# Ham-Dip-V2-005.net
KiCad netlist of a schematic drawn in EAGLE
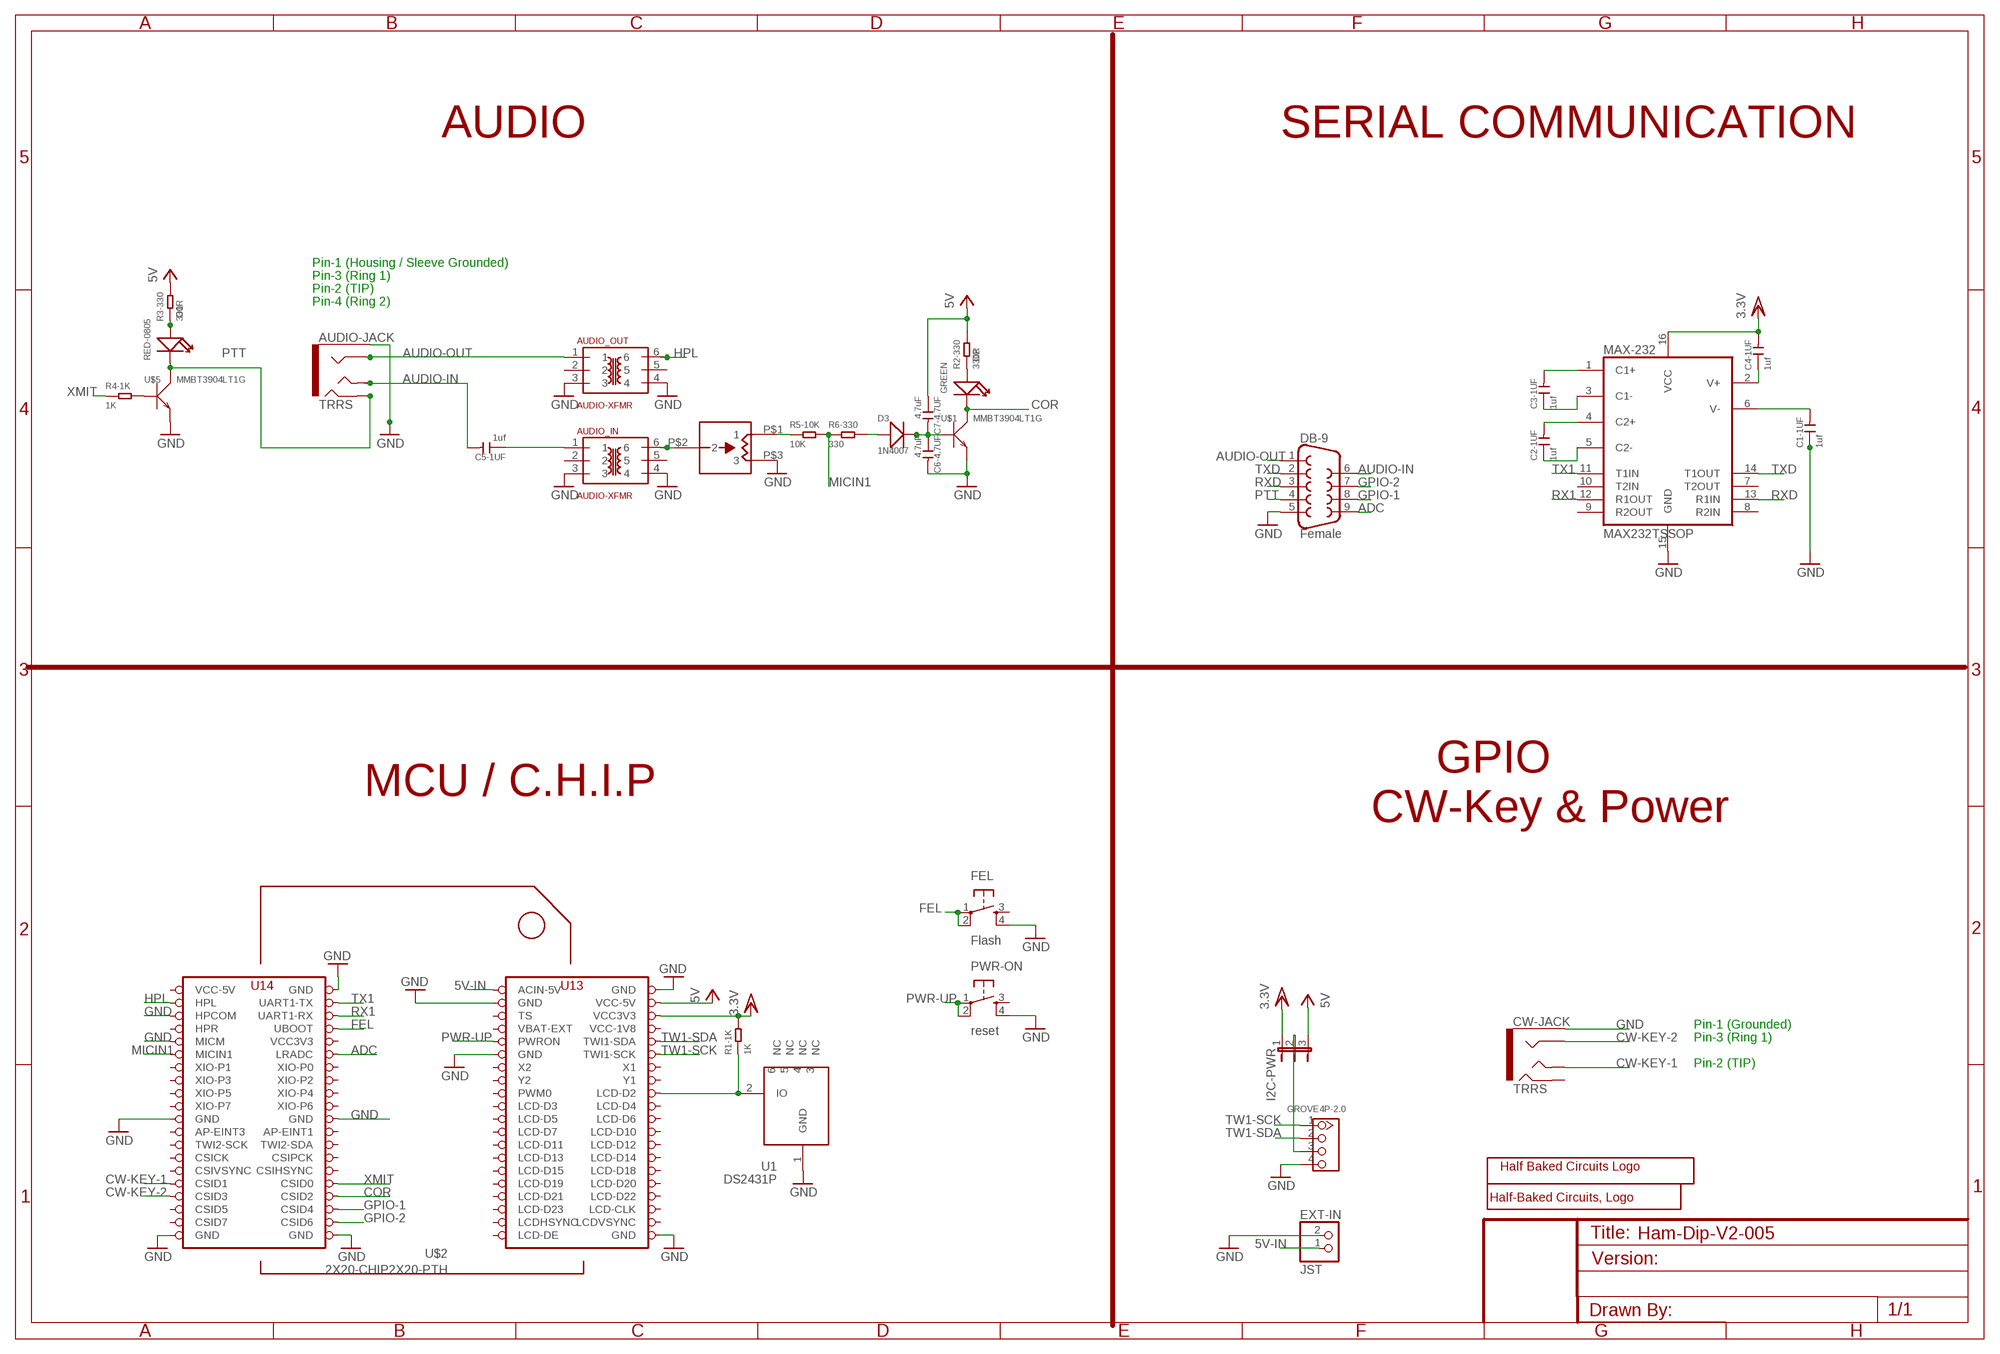
[diagram p0: schematic, sheet 1]

(export (version "E")
  (design (tool "Eeschema 10.0.6"))
  (components
    (comp (ref "AUDIO-JACK")
      (value "TRRS")
      (footprint "eagle-import:AUDIO-JACK-TRRS-SMD")
      (libsource (lib "eagle-import") (part "AUDIO-JACK3"))
    )
    (comp (ref "AUDIO_IN")
      (value "AUDIO-XFMR")
      (footprint "eagle-import:SM-LP-5001")
      (libsource (lib "eagle-import") (part "SM-LP-5001"))
    )
    (comp (ref "AUDIO_OUT")
      (value "AUDIO-XFMR")
      (footprint "eagle-import:SM-LP-5001")
      (libsource (lib "eagle-import") (part "SM-LP-5001"))
    )
    (comp (ref "C1-1UF")
      (value "1uf")
      (footprint "eagle-import:C0805")
      (fields (field (name "MPN") "CC0805KKX7R8BB105"))
      (libsource (lib "eagle-import") (part "CERAMIC-1UF-25V-10%-X7R(0805)"))
    )
    (comp (ref "C2-1UF")
      (value "1uf")
      (footprint "eagle-import:C0805")
      (fields (field (name "MPN") "CC0805KKX7R8BB105"))
      (libsource (lib "eagle-import") (part "CERAMIC-1UF-25V-10%-X7R(0805)"))
    )
    (comp (ref "C3-1UF")
      (value "1uf")
      (footprint "eagle-import:C0805")
      (fields (field (name "MPN") "CC0805KKX7R8BB105"))
      (libsource (lib "eagle-import") (part "CERAMIC-1UF-25V-10%-X7R(0805)"))
    )
    (comp (ref "C4-1UF")
      (value "1uf")
      (footprint "eagle-import:C0805")
      (fields (field (name "MPN") "CC0805KKX7R8BB105"))
      (libsource (lib "eagle-import") (part "CERAMIC-1UF-25V-10%-X7R(0805)"))
    )
    (comp (ref "C5-1UF")
      (value "1uf")
      (footprint "eagle-import:C0805")
      (fields (field (name "MPN") "CC0805KKX7R8BB105"))
      (libsource (lib "eagle-import") (part "CERAMIC-1UF-25V-10%-X7R(0805)"))
    )
    (comp (ref "C6-4.7UF")
      (value "4.7uF")
      (footprint "eagle-import:C0805")
      (fields (field (name "MPN") "CC0805KKX7R8BB105"))
      (libsource (lib "eagle-import") (part "CERAMIC-1UF-25V-10%-X7R(0805)"))
    )
    (comp (ref "C7-4.7UF")
      (value "4.7uF")
      (footprint "eagle-import:C0805")
      (fields (field (name "MPN") "CC0805KKX7R8BB105"))
      (libsource (lib "eagle-import") (part "CERAMIC-1UF-25V-10%-X7R(0805)"))
    )
    (comp (ref "CW-JACK")
      (value "TRRS")
      (footprint "eagle-import:AUDIO-JACK-TRRS-SMD")
      (libsource (lib "eagle-import") (part "AUDIO-JACK3"))
    )
    (comp (ref "D1")
      (value "RED-0805")
      (footprint "eagle-import:LED-0805")
      (fields (field (name "MPN") "17-215SURC/S530-A2/TR8"))
      (libsource (lib "eagle-import") (part "SMD-LED-CLEAR-RED(0805)"))
    )
    (comp (ref "D2")
      (value "GREEN")
      (footprint "eagle-import:LED-0805")
      (fields (field (name "MPN") "17-215SURC/S530-A2/TR8"))
      (libsource (lib "eagle-import") (part "SMD-LED-CLEAR-RED(0805)"))
    )
    (comp (ref "D3")
      (value "1N4007")
      (footprint "eagle-import:DO-214AC")
      (libsource (lib "eagle-import") (part "DIODE-GEN-PURPOSE-1KV-1A(DO-214AC)"))
    )
    (comp (ref "DB-9")
      (value "Female")
      (footprint "eagle-import:DB9")
      (libsource (lib "eagle-import") (part "DB9FEMALE"))
    )
    (comp (ref "EXT-IN")
      (value "JST")
      (footprint "eagle-import:JST-PH-2-THM")
      (libsource (lib "eagle-import") (part "JST_2PIN-THM"))
    )
    (comp (ref "FEL")
      (value "Flash")
      (footprint "eagle-import:TACTILE_SWITCH_SMD")
      (libsource (lib "eagle-import") (part "TAC_SWITCHSMD"))
    )
    (comp (ref "GROVE")
      (value "4P-2.0")
      (footprint "eagle-import:HW4-2.0")
      (libsource (lib "eagle-import") (part "GROVE-CONNECTOR-DIP(4P-2.0)"))
    )
    (comp (ref "I2C-PWR")
      (value "JP2E")
      (footprint "eagle-import:JP2")
      (libsource (lib "eagle-import") (part "JP2E"))
    )
    (comp (ref "MAX-232")
      (value "MAX232TSSOP")
      (footprint "eagle-import:TSSOP16")
      (libsource (lib "eagle-import") (part "MAX232TSSOP"))
    )
    (comp (ref "MIC-LVL")
      (value "1K")
      (footprint "eagle-import:TC33X")
      (libsource (lib "eagle-import") (part "TC33X"))
    )
    (comp (ref "PWR-ON")
      (value "reset")
      (footprint "eagle-import:TACTILE_SWITCH_SMD")
      (libsource (lib "eagle-import") (part "TAC_SWITCHSMD"))
    )
    (comp (ref "R1-1K")
      (value "1K")
      (footprint "eagle-import:R0805")
      (fields (field (name "MPN") "RC0805JR-07220RL"))
      (libsource (lib "eagle-import") (part "SMD-RES-220R-5%-1/8W(0805)"))
    )
    (comp (ref "R2-330")
      (value "330R")
      (footprint "eagle-import:R0805")
      (fields (field (name "MPN") "RC0805JR-07220RL"))
      (libsource (lib "eagle-import") (part "SMD-RES-220R-5%-1/8W(0805)"))
    )
    (comp (ref "R3-330")
      (value "330R")
      (footprint "eagle-import:R0805")
      (fields (field (name "MPN") "RC0805JR-07220RL"))
      (libsource (lib "eagle-import") (part "SMD-RES-220R-5%-1/8W(0805)"))
    )
    (comp (ref "R4-1K")
      (value "1K")
      (footprint "eagle-import:R0805")
      (fields (field (name "MPN") "RC0805JR-07220RL"))
      (libsource (lib "eagle-import") (part "SMD-RES-220R-5%-1/8W(0805)"))
    )
    (comp (ref "R5-10K")
      (value "10K")
      (footprint "eagle-import:R0805")
      (fields (field (name "MPN") "RC0805FR-0710KL"))
      (libsource (lib "eagle-import") (part "SMD-RES-10K-1%-1/8W(0805)"))
    )
    (comp (ref "R6-330")
      (value "330")
      (footprint "eagle-import:R0805")
      (fields (field (name "MPN") "RC0805JR-07220RL"))
      (libsource (lib "eagle-import") (part "SMD-RES-220R-5%-1/8W(0805)"))
    )
    (comp (ref "U$1")
      (value "MMBT3904LT1G")
      (footprint "eagle-import:SOT-23")
      (libsource (lib "eagle-import") (part "SMD-TRANSISTORS-NPN-40V-200MA-MMBT3904LT1G(SOT-23)"))
    )
    (comp (ref "U$2")
      (value "2X20-CHIP2X20-PTH")
      (footprint "eagle-import:2X20CHIP-TH")
      (fields (field (name "VENDOR_PART_NUMBER") "AWHW40-G-SMD-R (single)"))
      (libsource (lib "eagle-import") (part "2X20-CHIP2X20-PTH-CHIP_A"))
    )
    (comp (ref "U$3")
      (value "HBC-LOGO")
      (footprint "eagle-import:HBC-LOGO")
      (libsource (lib "eagle-import") (part "HBC-LOGO"))
    )
    (comp (ref "U$4")
      (value "HAM-DIP")
      (footprint "eagle-import:HAM-DIP")
      (libsource (lib "eagle-import") (part "HAM-DIP"))
    )
    (comp (ref "U$5")
      (value "MMBT3904LT1G")
      (footprint "eagle-import:SOT-23")
      (libsource (lib "eagle-import") (part "SMD-TRANSISTORS-NPN-40V-200MA-MMBT3904LT1G(SOT-23)"))
    )
    (comp (ref "U1")
      (value "DS2431P")
      (footprint "eagle-import:TSOC6")
      (fields (field (name "MFG") "DIGIKEY") (field (name "VENDOR_PART_NUMBER") "DS2431P+T&R"))
      (libsource (lib "eagle-import") (part "DS2431P"))
    )
  )
  (nets
    (net (code "1") (name "/5V-IN") (class "Default")
      (node (ref "EXT-IN") (pin "1") (pinfunction "2_1") (pintype "passive"))
      (node (ref "U$2") (pin "CHG-IN") (pinfunction "ACIN-5V_CHG-IN") (pintype "passive"))
    )
    (net (code "2") (name "/ADC") (class "Default")
      (node (ref "DB-9") (pin "9") (pinfunction "9_9") (pintype "passive"))
      (node (ref "U$2") (pin "LRADC") (pinfunction "LRADC_LRADC") (pintype "passive"))
    )
    (net (code "3") (name "/AUDIO-IN") (class "Default")
      (node (ref "AUDIO-JACK") (pin "TIP") (pinfunction "TIP_TIP") (pintype "bidirectional"))
      (node (ref "C5-1UF") (pin "2") (pinfunction "2_2") (pintype "passive"))
      (node (ref "DB-9") (pin "6") (pinfunction "6_6") (pintype "passive"))
    )
    (net (code "4") (name "/AUDIO-OUT") (class "Default")
      (node (ref "AUDIO-JACK") (pin "RING1") (pinfunction "RING1_RING1") (pintype "bidirectional"))
      (node (ref "AUDIO_OUT") (pin "1") (pinfunction "1_1") (pintype "bidirectional"))
      (node (ref "DB-9") (pin "1") (pinfunction "1_1") (pintype "passive"))
    )
    (net (code "5") (name "/COR") (class "Default")
      (node (ref "D2") (pin "-") (pinfunction "-_-") (pintype "passive"))
      (node (ref "U$1") (pin "3") (pinfunction "C_3") (pintype "passive"))
      (node (ref "U$2") (pin "CSID2") (pinfunction "CSID2_CSID2") (pintype "passive"))
    )
    (net (code "6") (name "/CW-KEY-1") (class "Default")
      (node (ref "CW-JACK") (pin "TIP") (pinfunction "TIP_TIP") (pintype "bidirectional"))
      (node (ref "U$2") (pin "CSID1") (pinfunction "CSID1_CSID1") (pintype "passive"))
    )
    (net (code "7") (name "/CW-KEY-2") (class "Default")
      (node (ref "CW-JACK") (pin "RING1") (pinfunction "RING1_RING1") (pintype "bidirectional"))
      (node (ref "U$2") (pin "CSID3") (pinfunction "CSID3_CSID3") (pintype "passive"))
    )
    (net (code "8") (name "/FEL") (class "Default")
      (node (ref "FEL") (pin "1") (pinfunction "1_1") (pintype "passive"))
      (node (ref "FEL") (pin "2") (pinfunction "2_2") (pintype "passive"))
      (node (ref "U$2") (pin "FEL") (pinfunction "UBOOT_FEL") (pintype "passive"))
    )
    (net (code "9") (name "/GPIO-1") (class "Default")
      (node (ref "DB-9") (pin "8") (pinfunction "8_8") (pintype "passive"))
      (node (ref "U$2") (pin "CSID4") (pinfunction "CSID4_CSID4") (pintype "passive"))
    )
    (net (code "10") (name "/GPIO-2") (class "Default")
      (node (ref "DB-9") (pin "7") (pinfunction "7_7") (pintype "passive"))
      (node (ref "U$2") (pin "CSID6") (pinfunction "CSID6_CSID6") (pintype "passive"))
    )
    (net (code "11") (name "/HPL") (class "Default")
      (node (ref "AUDIO_OUT") (pin "6") (pinfunction "6_6") (pintype "bidirectional"))
      (node (ref "U$2") (pin "HPL") (pinfunction "HPL_HPL") (pintype "passive"))
    )
    (net (code "12") (name "/MICIN1") (class "Default")
      (node (ref "R5-10K") (pin "2") (pinfunction "2_2") (pintype "passive"))
      (node (ref "R6-330") (pin "1") (pinfunction "1_1") (pintype "passive"))
      (node (ref "U$2") (pin "MICIN1") (pinfunction "MICIN1_MICIN1") (pintype "passive"))
    )
    (net (code "13") (name "/PTT") (class "Default")
      (node (ref "AUDIO-JACK") (pin "RING2") (pinfunction "RING2_RING2") (pintype "bidirectional"))
      (node (ref "D1") (pin "-") (pinfunction "-_-") (pintype "passive"))
      (node (ref "DB-9") (pin "4") (pinfunction "4_4") (pintype "passive"))
      (node (ref "U$5") (pin "3") (pinfunction "C_3") (pintype "passive"))
    )
    (net (code "14") (name "/PWR-UP") (class "Default")
      (node (ref "PWR-ON") (pin "1") (pinfunction "1_1") (pintype "passive"))
      (node (ref "PWR-ON") (pin "2") (pinfunction "2_2") (pintype "passive"))
      (node (ref "U$2") (pin "PWRON") (pinfunction "PWRON_PWRON") (pintype "passive"))
    )
    (net (code "15") (name "/RX1") (class "Default")
      (node (ref "MAX-232") (pin "12") (pinfunction "R1OUT_12") (pintype "output"))
      (node (ref "U$2") (pin "UART1-RX") (pinfunction "UART1-RX_UART1-RX") (pintype "passive"))
    )
    (net (code "16") (name "/RXD") (class "Default")
      (node (ref "DB-9") (pin "3") (pinfunction "3_3") (pintype "passive"))
      (node (ref "MAX-232") (pin "13") (pinfunction "R1IN_13") (pintype "input"))
    )
    (net (code "17") (name "/TW1-SCK") (class "Default")
      (node (ref "GROVE") (pin "1") (pinfunction "1_1") (pintype "bidirectional"))
      (node (ref "U$2") (pin "TWI1-SCK") (pinfunction "TWI1-SCK_TWI1-SCK") (pintype "passive"))
    )
    (net (code "18") (name "/TW1-SDA") (class "Default")
      (node (ref "GROVE") (pin "2") (pinfunction "2_2") (pintype "bidirectional"))
      (node (ref "U$2") (pin "TWI1-SDA") (pinfunction "TWI1-SDA_TWI1-SDA") (pintype "passive"))
    )
    (net (code "19") (name "/TX1") (class "Default")
      (node (ref "MAX-232") (pin "11") (pinfunction "T1IN_11") (pintype "input"))
      (node (ref "U$2") (pin "UART1-TX") (pinfunction "UART1-TX_UART1-TX") (pintype "passive"))
    )
    (net (code "20") (name "/TXD") (class "Default")
      (node (ref "DB-9") (pin "2") (pinfunction "2_2") (pintype "passive"))
      (node (ref "MAX-232") (pin "14") (pinfunction "T1OUT_14") (pintype "output"))
    )
    (net (code "21") (name "/VCC-1V8") (class "Default")
      (node (ref "U$2") (pin "VCC1V8") (pinfunction "VCC-1V8_VCC1V8") (pintype "power_in"))
    )
    (net (code "22") (name "/VCC-5V") (class "Default")
      (node (ref "U$2") (pin "VCC5V@1") (pinfunction "VCC-5V_VCC5V@1") (pintype "power_in"))
    )
    (net (code "23") (name "/VCC3V3") (class "Default")
      (node (ref "U$2") (pin "VCC3V3@1") (pinfunction "VCC3V3_VCC3V3@1") (pintype "power_in"))
    )
    (net (code "24") (name "/XMIT") (class "Default")
      (node (ref "R4-1K") (pin "1") (pinfunction "1_1") (pintype "passive"))
      (node (ref "U$2") (pin "CSID0") (pinfunction "CSID0_CSID0") (pintype "passive"))
    )
    (net (code "25") (name "3.3V") (class "Default")
      (node (ref "C4-1UF") (pin "2") (pinfunction "2_2") (pintype "passive"))
      (node (ref "I2C-PWR") (pin "1") (pinfunction "1_1") (pintype "passive"))
      (node (ref "MAX-232") (pin "16") (pinfunction "VCC_16") (pintype "bidirectional"))
      (node (ref "R1-1K") (pin "2") (pinfunction "2_2") (pintype "passive"))
      (node (ref "U$2") (pin "VCC3V3") (pinfunction "VCC3V3_VCC3V3") (pintype "power_in"))
    )
    (net (code "26") (name "5V") (class "Default")
      (node (ref "C7-4.7UF") (pin "1") (pinfunction "1_1") (pintype "passive"))
      (node (ref "I2C-PWR") (pin "3") (pinfunction "3_3") (pintype "passive"))
      (node (ref "R2-330") (pin "2") (pinfunction "2_2") (pintype "passive"))
      (node (ref "R3-330") (pin "2") (pinfunction "2_2") (pintype "passive"))
      (node (ref "U$2") (pin "VCC5V@0") (pinfunction "VCC-5V_VCC5V@0") (pintype "power_in"))
    )
    (net (code "27") (name "GND") (class "Default")
      (node (ref "AUDIO-JACK") (pin "EARTH") (pinfunction "EARTH_EARTH") (pintype "bidirectional"))
      (node (ref "AUDIO_IN") (pin "3") (pinfunction "3_3") (pintype "bidirectional"))
      (node (ref "AUDIO_IN") (pin "4") (pinfunction "4_4") (pintype "bidirectional"))
      (node (ref "AUDIO_OUT") (pin "3") (pinfunction "3_3") (pintype "bidirectional"))
      (node (ref "AUDIO_OUT") (pin "4") (pinfunction "4_4") (pintype "bidirectional"))
      (node (ref "C1-1UF") (pin "1") (pinfunction "1_1") (pintype "passive"))
      (node (ref "C6-4.7UF") (pin "2") (pinfunction "2_2") (pintype "passive"))
      (node (ref "CW-JACK") (pin "EARTH") (pinfunction "EARTH_EARTH") (pintype "bidirectional"))
      (node (ref "DB-9") (pin "5") (pinfunction "5_5") (pintype "passive"))
      (node (ref "EXT-IN") (pin "2") (pinfunction "1_2") (pintype "passive"))
      (node (ref "FEL") (pin "4") (pinfunction "4_4") (pintype "passive"))
      (node (ref "GROVE") (pin "4") (pinfunction "4_4") (pintype "bidirectional"))
      (node (ref "MAX-232") (pin "15") (pinfunction "GND_15") (pintype "bidirectional"))
      (node (ref "MIC-LVL") (pin "P$3") (pinfunction "3_P$3") (pintype "bidirectional"))
      (node (ref "PWR-ON") (pin "4") (pinfunction "4_4") (pintype "passive"))
      (node (ref "U$1") (pin "2") (pinfunction "E_2") (pintype "passive"))
      (node (ref "U$2") (pin "GND@1") (pinfunction "GND_GND@1") (pintype "power_in"))
      (node (ref "U$2") (pin "GND@10") (pinfunction "GND_GND@10") (pintype "power_in"))
      (node (ref "U$2") (pin "GND@2") (pinfunction "GND_GND@2") (pintype "power_in"))
      (node (ref "U$2") (pin "GND@3") (pinfunction "GND_GND@3") (pintype "power_in"))
      (node (ref "U$2") (pin "GND@4") (pinfunction "GND_GND@4") (pintype "power_in"))
      (node (ref "U$2") (pin "GND@5") (pinfunction "GND_GND@5") (pintype "power_in"))
      (node (ref "U$2") (pin "GND@6") (pinfunction "GND_GND@6") (pintype "power_in"))
      (node (ref "U$2") (pin "GND@7") (pinfunction "GND_GND@7") (pintype "power_in"))
      (node (ref "U$2") (pin "GND@8") (pinfunction "GND_GND@8") (pintype "power_in"))
      (node (ref "U$2") (pin "HPCOM") (pinfunction "HPCOM_HPCOM") (pintype "passive"))
      (node (ref "U$2") (pin "MICM") (pinfunction "MICM_MICM") (pintype "passive"))
      (node (ref "U$5") (pin "2") (pinfunction "E_2") (pintype "passive"))
      (node (ref "U1") (pin "1") (pinfunction "GND_1") (pintype "bidirectional"))
    )
    (net (code "28") (name "Net-(AUDIO_IN-Pad1)") (class "Default")
      (node (ref "AUDIO_IN") (pin "1") (pinfunction "1_1") (pintype "bidirectional"))
      (node (ref "C5-1UF") (pin "1") (pinfunction "1_1") (pintype "passive"))
    )
    (net (code "29") (name "Net-(D1-Pad+)") (class "Default")
      (node (ref "D1") (pin "+") (pinfunction "+_+") (pintype "passive"))
      (node (ref "R3-330") (pin "1") (pinfunction "1_1") (pintype "passive"))
    )
    (net (code "30") (name "Net-(D2-Pad+)") (class "Default")
      (node (ref "D2") (pin "+") (pinfunction "+_+") (pintype "passive"))
      (node (ref "R2-330") (pin "1") (pinfunction "1_1") (pintype "passive"))
    )
    (net (code "31") (name "Net-(D3-+)") (class "Default")
      (node (ref "D3") (pin "1") (pinfunction "+_1") (pintype "passive"))
      (node (ref "R6-330") (pin "2") (pinfunction "2_2") (pintype "passive"))
    )
    (net (code "32") (name "Net-(D3--)") (class "Default")
      (node (ref "C6-4.7UF") (pin "1") (pinfunction "1_1") (pintype "passive"))
      (node (ref "C7-4.7UF") (pin "2") (pinfunction "2_2") (pintype "passive"))
      (node (ref "D3") (pin "2") (pinfunction "-_2") (pintype "passive"))
      (node (ref "U$1") (pin "1") (pinfunction "B_1") (pintype "passive"))
    )
    (net (code "33") (name "Net-(GROVE-Pad3)") (class "Default")
      (node (ref "GROVE") (pin "3") (pinfunction "3_3") (pintype "bidirectional"))
      (node (ref "I2C-PWR") (pin "2") (pinfunction "2_2") (pintype "passive"))
    )
    (net (code "34") (name "Net-(MAX-232-C1+)") (class "Default")
      (node (ref "C3-1UF") (pin "2") (pinfunction "2_2") (pintype "passive"))
      (node (ref "MAX-232") (pin "1") (pinfunction "C1+_1") (pintype "bidirectional"))
    )
    (net (code "35") (name "Net-(MAX-232-C1-)") (class "Default")
      (node (ref "C3-1UF") (pin "1") (pinfunction "1_1") (pintype "passive"))
      (node (ref "MAX-232") (pin "3") (pinfunction "C1-_3") (pintype "bidirectional"))
    )
    (net (code "36") (name "Net-(MAX-232-C2+)") (class "Default")
      (node (ref "C2-1UF") (pin "2") (pinfunction "2_2") (pintype "passive"))
      (node (ref "MAX-232") (pin "4") (pinfunction "C2+_4") (pintype "bidirectional"))
    )
    (net (code "37") (name "Net-(MAX-232-C2-)") (class "Default")
      (node (ref "C2-1UF") (pin "1") (pinfunction "1_1") (pintype "passive"))
      (node (ref "MAX-232") (pin "5") (pinfunction "C2-_5") (pintype "bidirectional"))
    )
    (net (code "38") (name "Net-(MAX-232-V+)") (class "Default")
      (node (ref "C4-1UF") (pin "1") (pinfunction "1_1") (pintype "passive"))
      (node (ref "MAX-232") (pin "2") (pinfunction "V+_2") (pintype "bidirectional"))
    )
    (net (code "39") (name "Net-(MAX-232-V-)") (class "Default")
      (node (ref "C1-1UF") (pin "2") (pinfunction "2_2") (pintype "passive"))
      (node (ref "MAX-232") (pin "6") (pinfunction "V-_6") (pintype "bidirectional"))
    )
    (net (code "40") (name "Net-(MIC-LVL-1)") (class "Default")
      (node (ref "MIC-LVL") (pin "P$1") (pinfunction "1_P$1") (pintype "bidirectional"))
      (node (ref "R5-10K") (pin "1") (pinfunction "1_1") (pintype "passive"))
    )
    (net (code "41") (name "Net-(MIC-LVL-2)") (class "Default")
      (node (ref "AUDIO_IN") (pin "6") (pinfunction "6_6") (pintype "bidirectional"))
      (node (ref "MIC-LVL") (pin "P$2") (pinfunction "2_P$2") (pintype "bidirectional"))
    )
    (net (code "42") (name "Net-(U$5-B)") (class "Default")
      (node (ref "R4-1K") (pin "2") (pinfunction "2_2") (pintype "passive"))
      (node (ref "U$5") (pin "1") (pinfunction "B_1") (pintype "passive"))
    )
    (net (code "43") (name "Net-(U1-IO)") (class "Default")
      (node (ref "R1-1K") (pin "1") (pinfunction "1_1") (pintype "passive"))
      (node (ref "U$2") (pin "LCD-D2") (pinfunction "LCD-D2_LCD-D2") (pintype "passive"))
      (node (ref "U1") (pin "2") (pinfunction "IO_2") (pintype "bidirectional"))
    )
    (net (code "44") (name "unconnected-(AUDIO_IN-Pad2)") (class "Default")
      (node (ref "AUDIO_IN") (pin "2") (pinfunction "2_2") (pintype "bidirectional"))
    )
    (net (code "45") (name "unconnected-(AUDIO_IN-Pad5)") (class "Default")
      (node (ref "AUDIO_IN") (pin "5") (pinfunction "5_5") (pintype "bidirectional"))
    )
    (net (code "46") (name "unconnected-(AUDIO_OUT-Pad2)") (class "Default")
      (node (ref "AUDIO_OUT") (pin "2") (pinfunction "2_2") (pintype "bidirectional"))
    )
    (net (code "47") (name "unconnected-(AUDIO_OUT-Pad5)") (class "Default")
      (node (ref "AUDIO_OUT") (pin "5") (pinfunction "5_5") (pintype "bidirectional"))
    )
    (net (code "48") (name "unconnected-(CW-JACK-PadRING2)") (class "Default")
      (node (ref "CW-JACK") (pin "RING2") (pinfunction "RING2_RING2") (pintype "bidirectional"))
    )
    (net (code "49") (name "unconnected-(FEL-Pad3)") (class "Default")
      (node (ref "FEL") (pin "3") (pinfunction "3_3") (pintype "passive"))
    )
    (net (code "50") (name "unconnected-(MAX-232-R2IN-Pad8)") (class "Default")
      (node (ref "MAX-232") (pin "8") (pinfunction "R2IN_8") (pintype "input"))
    )
    (net (code "51") (name "unconnected-(MAX-232-R2OUT-Pad9)") (class "Default")
      (node (ref "MAX-232") (pin "9") (pinfunction "R2OUT_9") (pintype "output"))
    )
    (net (code "52") (name "unconnected-(MAX-232-T2IN-Pad10)") (class "Default")
      (node (ref "MAX-232") (pin "10") (pinfunction "T2IN_10") (pintype "input"))
    )
    (net (code "53") (name "unconnected-(MAX-232-T2OUT-Pad7)") (class "Default")
      (node (ref "MAX-232") (pin "7") (pinfunction "T2OUT_7") (pintype "output"))
    )
    (net (code "54") (name "unconnected-(PWR-ON-Pad3)") (class "Default")
      (node (ref "PWR-ON") (pin "3") (pinfunction "3_3") (pintype "passive"))
    )
    (net (code "55") (name "unconnected-(U$2-LCDHSYNC-PadLCD-HSYNC)") (class "Default")
      (node (ref "U$2") (pin "LCD-HSYNC") (pinfunction "LCDHSYNC_LCD-HSYNC") (pintype "passive"))
    )
    (net (code "56") (name "unconnected-(U$2-LCDVSYNC-PadLCD-VSYNC)") (class "Default")
      (node (ref "U$2") (pin "LCD-VSYNC") (pinfunction "LCDVSYNC_LCD-VSYNC") (pintype "passive"))
    )
    (net (code "57") (name "unconnected-(U$2-PadAP-EINT1)") (class "Default")
      (node (ref "U$2") (pin "AP-EINT1") (pinfunction "AP-EINT1_AP-EINT1") (pintype "passive"))
    )
    (net (code "58") (name "unconnected-(U$2-PadAP-EINT3)") (class "Default")
      (node (ref "U$2") (pin "AP-EINT3") (pinfunction "AP-EINT3_AP-EINT3") (pintype "passive"))
    )
    (net (code "59") (name "unconnected-(U$2-PadCSICK)") (class "Default")
      (node (ref "U$2") (pin "CSICK") (pinfunction "CSICK_CSICK") (pintype "passive"))
    )
    (net (code "60") (name "unconnected-(U$2-PadCSID5)") (class "Default")
      (node (ref "U$2") (pin "CSID5") (pinfunction "CSID5_CSID5") (pintype "passive"))
    )
    (net (code "61") (name "unconnected-(U$2-PadCSID7)") (class "Default")
      (node (ref "U$2") (pin "CSID7") (pinfunction "CSID7_CSID7") (pintype "passive"))
    )
    (net (code "62") (name "unconnected-(U$2-PadCSIHSYNC)") (class "Default")
      (node (ref "U$2") (pin "CSIHSYNC") (pinfunction "CSIHSYNC_CSIHSYNC") (pintype "passive"))
    )
    (net (code "63") (name "unconnected-(U$2-PadCSIPCK)") (class "Default")
      (node (ref "U$2") (pin "CSIPCK") (pinfunction "CSIPCK_CSIPCK") (pintype "passive"))
    )
    (net (code "64") (name "unconnected-(U$2-PadCSIVSYNC)") (class "Default")
      (node (ref "U$2") (pin "CSIVSYNC") (pinfunction "CSIVSYNC_CSIVSYNC") (pintype "passive"))
    )
    (net (code "65") (name "unconnected-(U$2-PadHPR)") (class "Default")
      (node (ref "U$2") (pin "HPR") (pinfunction "HPR_HPR") (pintype "passive"))
    )
    (net (code "66") (name "unconnected-(U$2-PadLCD-CLK)") (class "Default")
      (node (ref "U$2") (pin "LCD-CLK") (pinfunction "LCD-CLK_LCD-CLK") (pintype "passive"))
    )
    (net (code "67") (name "unconnected-(U$2-PadLCD-D3)") (class "Default")
      (node (ref "U$2") (pin "LCD-D3") (pinfunction "LCD-D3_LCD-D3") (pintype "passive"))
    )
    (net (code "68") (name "unconnected-(U$2-PadLCD-D4)") (class "Default")
      (node (ref "U$2") (pin "LCD-D4") (pinfunction "LCD-D4_LCD-D4") (pintype "passive"))
    )
    (net (code "69") (name "unconnected-(U$2-PadLCD-D5)") (class "Default")
      (node (ref "U$2") (pin "LCD-D5") (pinfunction "LCD-D5_LCD-D5") (pintype "passive"))
    )
    (net (code "70") (name "unconnected-(U$2-PadLCD-D6)") (class "Default")
      (node (ref "U$2") (pin "LCD-D6") (pinfunction "LCD-D6_LCD-D6") (pintype "passive"))
    )
    (net (code "71") (name "unconnected-(U$2-PadLCD-D7)") (class "Default")
      (node (ref "U$2") (pin "LCD-D7") (pinfunction "LCD-D7_LCD-D7") (pintype "passive"))
    )
    (net (code "72") (name "unconnected-(U$2-PadLCD-D10)") (class "Default")
      (node (ref "U$2") (pin "LCD-D10") (pinfunction "LCD-D10_LCD-D10") (pintype "passive"))
    )
    (net (code "73") (name "unconnected-(U$2-PadLCD-D11)") (class "Default")
      (node (ref "U$2") (pin "LCD-D11") (pinfunction "LCD-D11_LCD-D11") (pintype "passive"))
    )
    (net (code "74") (name "unconnected-(U$2-PadLCD-D12)") (class "Default")
      (node (ref "U$2") (pin "LCD-D12") (pinfunction "LCD-D12_LCD-D12") (pintype "passive"))
    )
    (net (code "75") (name "unconnected-(U$2-PadLCD-D13)") (class "Default")
      (node (ref "U$2") (pin "LCD-D13") (pinfunction "LCD-D13_LCD-D13") (pintype "passive"))
    )
    (net (code "76") (name "unconnected-(U$2-PadLCD-D14)") (class "Default")
      (node (ref "U$2") (pin "LCD-D14") (pinfunction "LCD-D14_LCD-D14") (pintype "passive"))
    )
    (net (code "77") (name "unconnected-(U$2-PadLCD-D15)") (class "Default")
      (node (ref "U$2") (pin "LCD-D15") (pinfunction "LCD-D15_LCD-D15") (pintype "passive"))
    )
    (net (code "78") (name "unconnected-(U$2-PadLCD-D18)") (class "Default")
      (node (ref "U$2") (pin "LCD-D18") (pinfunction "LCD-D18_LCD-D18") (pintype "passive"))
    )
    (net (code "79") (name "unconnected-(U$2-PadLCD-D19)") (class "Default")
      (node (ref "U$2") (pin "LCD-D19") (pinfunction "LCD-D19_LCD-D19") (pintype "passive"))
    )
    (net (code "80") (name "unconnected-(U$2-PadLCD-D20)") (class "Default")
      (node (ref "U$2") (pin "LCD-D20") (pinfunction "LCD-D20_LCD-D20") (pintype "passive"))
    )
    (net (code "81") (name "unconnected-(U$2-PadLCD-D21)") (class "Default")
      (node (ref "U$2") (pin "LCD-D21") (pinfunction "LCD-D21_LCD-D21") (pintype "passive"))
    )
    (net (code "82") (name "unconnected-(U$2-PadLCD-D22)") (class "Default")
      (node (ref "U$2") (pin "LCD-D22") (pinfunction "LCD-D22_LCD-D22") (pintype "passive"))
    )
    (net (code "83") (name "unconnected-(U$2-PadLCD-D23)") (class "Default")
      (node (ref "U$2") (pin "LCD-D23") (pinfunction "LCD-D23_LCD-D23") (pintype "passive"))
    )
    (net (code "84") (name "unconnected-(U$2-PadLCD-DE)") (class "Default")
      (node (ref "U$2") (pin "LCD-DE") (pinfunction "LCD-DE_LCD-DE") (pintype "passive"))
    )
    (net (code "85") (name "unconnected-(U$2-PadPWM0)") (class "Default")
      (node (ref "U$2") (pin "PWM0") (pinfunction "PWM0_PWM0") (pintype "passive"))
    )
    (net (code "86") (name "unconnected-(U$2-PadTS)") (class "Default")
      (node (ref "U$2") (pin "TS") (pinfunction "TS_TS") (pintype "passive"))
    )
    (net (code "87") (name "unconnected-(U$2-PadTWI2-SCK)") (class "Default")
      (node (ref "U$2") (pin "TWI2-SCK") (pinfunction "TWI2-SCK_TWI2-SCK") (pintype "passive"))
    )
    (net (code "88") (name "unconnected-(U$2-PadTWI2-SDA)") (class "Default")
      (node (ref "U$2") (pin "TWI2-SDA") (pinfunction "TWI2-SDA_TWI2-SDA") (pintype "passive"))
    )
    (net (code "89") (name "unconnected-(U$2-PadX1)") (class "Default")
      (node (ref "U$2") (pin "X1") (pinfunction "X1_X1") (pintype "passive"))
    )
    (net (code "90") (name "unconnected-(U$2-PadX2)") (class "Default")
      (node (ref "U$2") (pin "X2") (pinfunction "X2_X2") (pintype "passive"))
    )
    (net (code "91") (name "unconnected-(U$2-PadXIO-P0)") (class "Default")
      (node (ref "U$2") (pin "XIO-P0") (pinfunction "XIO-P0_XIO-P0") (pintype "passive"))
    )
    (net (code "92") (name "unconnected-(U$2-PadXIO-P1)") (class "Default")
      (node (ref "U$2") (pin "XIO-P1") (pinfunction "XIO-P1_XIO-P1") (pintype "passive"))
    )
    (net (code "93") (name "unconnected-(U$2-PadXIO-P2)") (class "Default")
      (node (ref "U$2") (pin "XIO-P2") (pinfunction "XIO-P2_XIO-P2") (pintype "passive"))
    )
    (net (code "94") (name "unconnected-(U$2-PadXIO-P3)") (class "Default")
      (node (ref "U$2") (pin "XIO-P3") (pinfunction "XIO-P3_XIO-P3") (pintype "passive"))
    )
    (net (code "95") (name "unconnected-(U$2-PadXIO-P4)") (class "Default")
      (node (ref "U$2") (pin "XIO-P4") (pinfunction "XIO-P4_XIO-P4") (pintype "passive"))
    )
    (net (code "96") (name "unconnected-(U$2-PadXIO-P5)") (class "Default")
      (node (ref "U$2") (pin "XIO-P5") (pinfunction "XIO-P5_XIO-P5") (pintype "passive"))
    )
    (net (code "97") (name "unconnected-(U$2-PadXIO-P6)") (class "Default")
      (node (ref "U$2") (pin "XIO-P6") (pinfunction "XIO-P6_XIO-P6") (pintype "passive"))
    )
    (net (code "98") (name "unconnected-(U$2-PadXIO-P7)") (class "Default")
      (node (ref "U$2") (pin "XIO-P7") (pinfunction "XIO-P7_XIO-P7") (pintype "passive"))
    )
    (net (code "99") (name "unconnected-(U$2-PadY1)") (class "Default")
      (node (ref "U$2") (pin "Y1") (pinfunction "Y1_Y1") (pintype "passive"))
    )
    (net (code "100") (name "unconnected-(U$2-PadY2)") (class "Default")
      (node (ref "U$2") (pin "Y2") (pinfunction "Y2_Y2") (pintype "passive"))
    )
    (net (code "101") (name "unconnected-(U$2-VBAT-EXT-PadBAT)") (class "Default")
      (node (ref "U$2") (pin "BAT") (pinfunction "VBAT-EXT_BAT") (pintype "passive"))
    )
    (net (code "102") (name "unconnected-(U1-NC-Pad3)") (class "Default")
      (node (ref "U1") (pin "3") (pinfunction "NC_3") (pintype "bidirectional"))
    )
    (net (code "103") (name "unconnected-(U1-NC-Pad4)") (class "Default")
      (node (ref "U1") (pin "4") (pinfunction "NC_4") (pintype "bidirectional"))
    )
    (net (code "104") (name "unconnected-(U1-NC-Pad5)") (class "Default")
      (node (ref "U1") (pin "5") (pinfunction "NC_5") (pintype "bidirectional"))
    )
    (net (code "105") (name "unconnected-(U1-NC-Pad6)") (class "Default")
      (node (ref "U1") (pin "6") (pinfunction "NC_6") (pintype "bidirectional"))
    )
  )
)
